# PCB_V1.net
KiCad netlist of a schematic drawn in Altium Designer
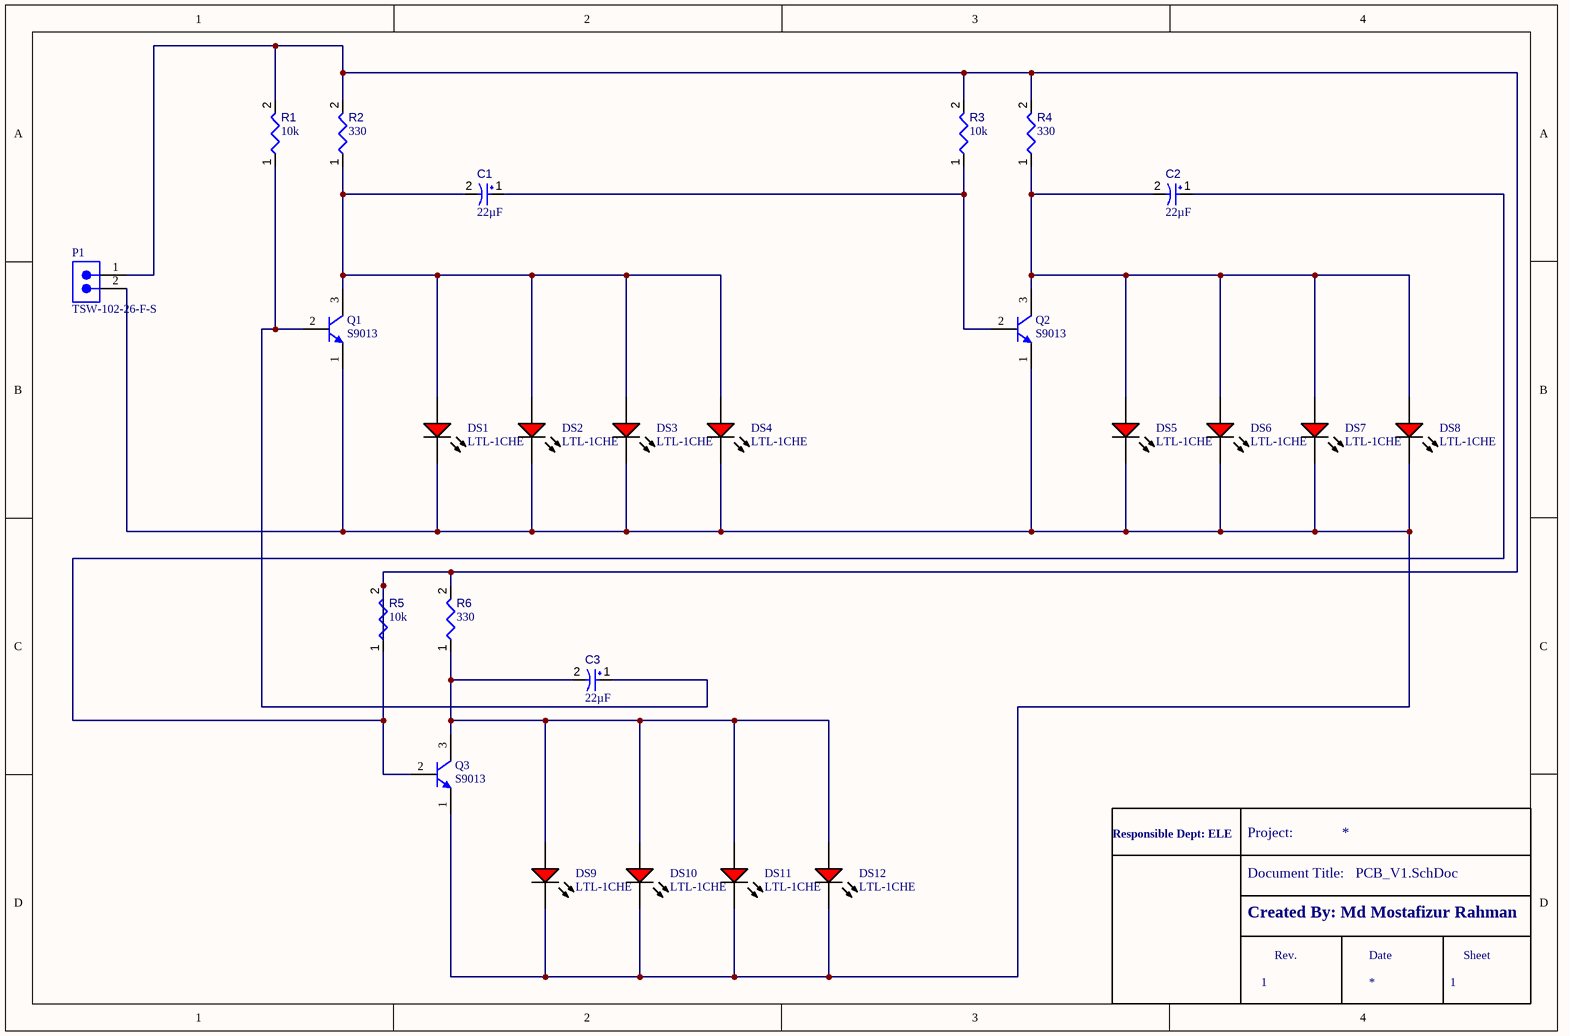
[diagram p0: PCB_V1.SchDoc]

(export (version "E")
  (design (tool "Eeschema 10.0.6"))
  (components
    (comp (ref "*") (value "HSHL Title Block") (libsource (lib "Schlib1") (part "HSHL Title Block")))
    (comp (ref "C1")
      (value "22µF")
      (footprint "CAPPR55-200-1100X500X1200")
      (description "Aluminum Electrolytic Capacitor, 22 uF, +/- 20%, 50 V, -40 to 85 degC, 2-Pin THD, RoHS, Bulk")
      (fields (field (name "MANUFACTURER") "Panasonic") (field (name "TOLERANCE") "20%"))
      (libsource (lib "Md Mostafizur Rahman") (part "CAP-P-2"))
    )
    (comp (ref "C2")
      (value "22µF")
      (footprint "CAPPR55-200-1100X500X1200")
      (description "Aluminum Electrolytic Capacitor, 22 uF, +/- 20%, 50 V, -40 to 85 degC, 2-Pin THD, RoHS, Bulk")
      (fields (field (name "MANUFACTURER") "Panasonic") (field (name "TOLERANCE") "20%"))
      (libsource (lib "Md Mostafizur Rahman") (part "CAP-P-2"))
    )
    (comp (ref "C3")
      (value "22µF")
      (footprint "CAPPR55-200-1100X500X1200")
      (description "Aluminum Electrolytic Capacitor, 22 uF, +/- 20%, 50 V, -40 to 85 degC, 2-Pin THD, RoHS, Bulk")
      (fields (field (name "MANUFACTURER") "Panasonic") (field (name "TOLERANCE") "20%"))
      (libsource (lib "Md Mostafizur Rahman") (part "CAP-P-2"))
    )
    (comp (ref "DS1")
      (value "LTL-1CHE")
      (footprint "INDPR60-254-520X380X650")
      (description "LED Uni-Color Red, 100 mW, 30 mA, -55 to 100 degC, 2-Pin THD, RoHS, Bulk")
      (fields (field (name "MANUFACTURER") "Lite-On"))
      (libsource (lib "Md Mostafizur Rahman") (part "LED-RED-AK-2"))
    )
    (comp (ref "DS2")
      (value "LTL-1CHE")
      (footprint "INDPR60-254-520X380X650")
      (description "LED Uni-Color Red, 100 mW, 30 mA, -55 to 100 degC, 2-Pin THD, RoHS, Bulk")
      (fields (field (name "MANUFACTURER") "Lite-On"))
      (libsource (lib "Md Mostafizur Rahman") (part "LED-RED-AK-2"))
    )
    (comp (ref "DS3")
      (value "LTL-1CHE")
      (footprint "INDPR60-254-520X380X650")
      (description "LED Uni-Color Red, 100 mW, 30 mA, -55 to 100 degC, 2-Pin THD, RoHS, Bulk")
      (fields (field (name "MANUFACTURER") "Lite-On"))
      (libsource (lib "Md Mostafizur Rahman") (part "LED-RED-AK-2"))
    )
    (comp (ref "DS4")
      (value "LTL-1CHE")
      (footprint "INDPR60-254-520X380X650")
      (description "LED Uni-Color Red, 100 mW, 30 mA, -55 to 100 degC, 2-Pin THD, RoHS, Bulk")
      (fields (field (name "MANUFACTURER") "Lite-On"))
      (libsource (lib "Md Mostafizur Rahman") (part "LED-RED-AK-2"))
    )
    (comp (ref "DS5")
      (value "LTL-1CHE")
      (footprint "INDPR60-254-520X380X650")
      (description "LED Uni-Color Red, 100 mW, 30 mA, -55 to 100 degC, 2-Pin THD, RoHS, Bulk")
      (fields (field (name "MANUFACTURER") "Lite-On"))
      (libsource (lib "Md Mostafizur Rahman") (part "LED-RED-AK-2"))
    )
    (comp (ref "DS6")
      (value "LTL-1CHE")
      (footprint "INDPR60-254-520X380X650")
      (description "LED Uni-Color Red, 100 mW, 30 mA, -55 to 100 degC, 2-Pin THD, RoHS, Bulk")
      (fields (field (name "MANUFACTURER") "Lite-On"))
      (libsource (lib "Md Mostafizur Rahman") (part "LED-RED-AK-2"))
    )
    (comp (ref "DS7")
      (value "LTL-1CHE")
      (footprint "INDPR60-254-520X380X650")
      (description "LED Uni-Color Red, 100 mW, 30 mA, -55 to 100 degC, 2-Pin THD, RoHS, Bulk")
      (fields (field (name "MANUFACTURER") "Lite-On"))
      (libsource (lib "Md Mostafizur Rahman") (part "LED-RED-AK-2"))
    )
    (comp (ref "DS8")
      (value "LTL-1CHE")
      (footprint "INDPR60-254-520X380X650")
      (description "LED Uni-Color Red, 100 mW, 30 mA, -55 to 100 degC, 2-Pin THD, RoHS, Bulk")
      (fields (field (name "MANUFACTURER") "Lite-On"))
      (libsource (lib "Md Mostafizur Rahman") (part "LED-RED-AK-2"))
    )
    (comp (ref "DS9")
      (value "LTL-1CHE")
      (footprint "INDPR60-254-520X380X650")
      (description "LED Uni-Color Red, 100 mW, 30 mA, -55 to 100 degC, 2-Pin THD, RoHS, Bulk")
      (fields (field (name "MANUFACTURER") "Lite-On"))
      (libsource (lib "Md Mostafizur Rahman") (part "LED-RED-AK-2"))
    )
    (comp (ref "DS10")
      (value "LTL-1CHE")
      (footprint "INDPR60-254-520X380X650")
      (description "LED Uni-Color Red, 100 mW, 30 mA, -55 to 100 degC, 2-Pin THD, RoHS, Bulk")
      (fields (field (name "MANUFACTURER") "Lite-On"))
      (libsource (lib "Md Mostafizur Rahman") (part "LED-RED-AK-2"))
    )
    (comp (ref "DS11")
      (value "LTL-1CHE")
      (footprint "INDPR60-254-520X380X650")
      (description "LED Uni-Color Red, 100 mW, 30 mA, -55 to 100 degC, 2-Pin THD, RoHS, Bulk")
      (fields (field (name "MANUFACTURER") "Lite-On"))
      (libsource (lib "Md Mostafizur Rahman") (part "LED-RED-AK-2"))
    )
    (comp (ref "DS12")
      (value "LTL-1CHE")
      (footprint "INDPR60-254-520X380X650")
      (description "LED Uni-Color Red, 100 mW, 30 mA, -55 to 100 degC, 2-Pin THD, RoHS, Bulk")
      (fields (field (name "MANUFACTURER") "Lite-On"))
      (libsource (lib "Md Mostafizur Rahman") (part "LED-RED-AK-2"))
    )
    (comp (ref "P1")
      (value "TSW-102-26-F-S")
      (footprint "SMTC-TSW-102-26-XX-S")
      (description "0.025\" SQ Post Header, Through-hole, Vertical, -55 to 125 degC, 2.54 mm Pitch, 2-Pin, Male, RoHS")
      (fields (field (name "MANUFACTURER") "Samtec"))
      (libsource (lib "Altium Content Vault") (part "SMTC-TSW-102-X-X-S-X"))
    )
    (comp (ref "Q1")
      (value "S9013")
      (footprint "JSCJ-TO-92-3_V")
      (description "Transistor, NPN, 0.1 uA, 150 MHz, 3-Pin TO-92")
      (fields (field (name "MANUFACTURER") "Jiangsu Changjiang Electronics Technology"))
      (libsource (lib "Md Mostafizur Rahman") (part "BJT-NPN-EBC-3"))
    )
    (comp (ref "Q2")
      (value "S9013")
      (footprint "JSCJ-TO-92-3_V")
      (description "Transistor, NPN, 0.1 uA, 150 MHz, 3-Pin TO-92")
      (fields (field (name "MANUFACTURER") "Jiangsu Changjiang Electronics Technology"))
      (libsource (lib "Md Mostafizur Rahman") (part "BJT-NPN-EBC-3"))
    )
    (comp (ref "Q3")
      (value "S9013")
      (footprint "JSCJ-TO-92-3_V")
      (description "Transistor, NPN, 0.1 uA, 150 MHz, 3-Pin TO-92")
      (fields (field (name "MANUFACTURER") "Jiangsu Changjiang Electronics Technology"))
      (libsource (lib "Md Mostafizur Rahman") (part "BJT-NPN-EBC-3"))
    )
    (comp (ref "R1")
      (value "10k")
      (footprint "RESA60-630X240")
      (description "Axial Resistor, 10 KOhm, +/- 1%, 0.25 W, -55 to 155 degC, 2-Pin THD, RoHS, Bulk")
      (fields (field (name "TOLERANCE") "1%") (field (name "POWER") "250mW"))
      (libsource (lib "Md Mostafizur Rahman") (part "RES-2"))
    )
    (comp (ref "R2")
      (value "330")
      (description "Fixed Resistor, Carbon Film, 0.125W, 330ohm, 250V, 5% +/-Tol, -400, 0ppm/Cel, Through Hole Mount")
      (fields (field (name "TOLERANCE") "5%") (field (name "Comment") "CF18JT330R"))
      (libsource (lib "Md Mostafizur Rahman") (part "RES-2"))
    )
    (comp (ref "R3")
      (value "10k")
      (footprint "RESA60-630X240")
      (description "Axial Resistor, 10 KOhm, +/- 1%, 0.25 W, -55 to 155 degC, 2-Pin THD, RoHS, Bulk")
      (fields (field (name "TOLERANCE") "1%") (field (name "POWER") "250mW"))
      (libsource (lib "Md Mostafizur Rahman") (part "RES-2"))
    )
    (comp (ref "R4")
      (value "330")
      (description "Fixed Resistor, Carbon Film, 0.125W, 330ohm, 250V, 5% +/-Tol, -400, 0ppm/Cel, Through Hole Mount")
      (fields (field (name "TOLERANCE") "5%") (field (name "Comment") "CF18JT330R"))
      (libsource (lib "Md Mostafizur Rahman") (part "RES-2"))
    )
    (comp (ref "R5")
      (value "10k")
      (footprint "RESA60-630X240")
      (description "Axial Resistor, 10 KOhm, +/- 1%, 0.25 W, -55 to 155 degC, 2-Pin THD, RoHS, Bulk")
      (fields (field (name "TOLERANCE") "1%") (field (name "POWER") "250mW"))
      (libsource (lib "Md Mostafizur Rahman") (part "RES-2"))
    )
    (comp (ref "R6")
      (value "330")
      (description "Fixed Resistor, Carbon Film, 0.125W, 330ohm, 250V, 5% +/-Tol, -400, 0ppm/Cel, Through Hole Mount")
      (fields (field (name "TOLERANCE") "5%") (field (name "Comment") "CF18JT330R"))
      (libsource (lib "Md Mostafizur Rahman") (part "RES-2"))
    )
  )
  (nets
    (net (code "1") (name "Net-(DS1-A)") (class "Default")
      (node (ref "C1") (pin "2") (pinfunction "2_2") (pintype "passive"))
      (node (ref "DS1") (pin "1") (pinfunction "A_1") (pintype "passive"))
      (node (ref "DS2") (pin "1") (pinfunction "A_1") (pintype "passive"))
      (node (ref "DS3") (pin "1") (pinfunction "A_1") (pintype "passive"))
      (node (ref "DS4") (pin "1") (pinfunction "A_1") (pintype "passive"))
      (node (ref "Q1") (pin "3") (pinfunction "C_3") (pintype "passive"))
      (node (ref "R2") (pin "1") (pinfunction "1_1") (pintype "passive"))
    )
    (net (code "2") (name "Net-(DS1-K)") (class "Default")
      (node (ref "DS1") (pin "2") (pinfunction "K_2") (pintype "passive"))
      (node (ref "DS10") (pin "2") (pinfunction "K_2") (pintype "passive"))
      (node (ref "DS11") (pin "2") (pinfunction "K_2") (pintype "passive"))
      (node (ref "DS12") (pin "2") (pinfunction "K_2") (pintype "passive"))
      (node (ref "DS2") (pin "2") (pinfunction "K_2") (pintype "passive"))
      (node (ref "DS3") (pin "2") (pinfunction "K_2") (pintype "passive"))
      (node (ref "DS4") (pin "2") (pinfunction "K_2") (pintype "passive"))
      (node (ref "DS5") (pin "2") (pinfunction "K_2") (pintype "passive"))
      (node (ref "DS6") (pin "2") (pinfunction "K_2") (pintype "passive"))
      (node (ref "DS7") (pin "2") (pinfunction "K_2") (pintype "passive"))
      (node (ref "DS8") (pin "2") (pinfunction "K_2") (pintype "passive"))
      (node (ref "DS9") (pin "2") (pinfunction "K_2") (pintype "passive"))
      (node (ref "P1") (pin "2") (pinfunction "2_2") (pintype "passive"))
      (node (ref "Q1") (pin "1") (pinfunction "E_1") (pintype "passive"))
      (node (ref "Q2") (pin "1") (pinfunction "E_1") (pintype "passive"))
      (node (ref "Q3") (pin "1") (pinfunction "E_1") (pintype "passive"))
    )
    (net (code "3") (name "Net-(DS5-A)") (class "Default")
      (node (ref "C2") (pin "2") (pinfunction "2_2") (pintype "passive"))
      (node (ref "DS5") (pin "1") (pinfunction "A_1") (pintype "passive"))
      (node (ref "DS6") (pin "1") (pinfunction "A_1") (pintype "passive"))
      (node (ref "DS7") (pin "1") (pinfunction "A_1") (pintype "passive"))
      (node (ref "DS8") (pin "1") (pinfunction "A_1") (pintype "passive"))
      (node (ref "Q2") (pin "3") (pinfunction "C_3") (pintype "passive"))
      (node (ref "R4") (pin "1") (pinfunction "1_1") (pintype "passive"))
    )
    (net (code "4") (name "Net-(DS10-A)") (class "Default")
      (node (ref "C3") (pin "2") (pinfunction "2_2") (pintype "passive"))
      (node (ref "DS10") (pin "1") (pinfunction "A_1") (pintype "passive"))
      (node (ref "DS11") (pin "1") (pinfunction "A_1") (pintype "passive"))
      (node (ref "DS12") (pin "1") (pinfunction "A_1") (pintype "passive"))
      (node (ref "DS9") (pin "1") (pinfunction "A_1") (pintype "passive"))
      (node (ref "Q3") (pin "3") (pinfunction "C_3") (pintype "passive"))
      (node (ref "R6") (pin "1") (pinfunction "1_1") (pintype "passive"))
    )
    (net (code "5") (name "Net-(P1-Pad1)") (class "Default")
      (node (ref "P1") (pin "1") (pinfunction "1_1") (pintype "passive"))
      (node (ref "R1") (pin "2") (pinfunction "2_2") (pintype "passive"))
      (node (ref "R2") (pin "2") (pinfunction "2_2") (pintype "passive"))
      (node (ref "R3") (pin "2") (pinfunction "2_2") (pintype "passive"))
      (node (ref "R4") (pin "2") (pinfunction "2_2") (pintype "passive"))
      (node (ref "R5") (pin "2") (pinfunction "2_2") (pintype "passive"))
      (node (ref "R6") (pin "2") (pinfunction "2_2") (pintype "passive"))
    )
    (net (code "6") (name "Net-(Q1-B)") (class "Default")
      (node (ref "C3") (pin "1") (pinfunction "1_1") (pintype "passive"))
      (node (ref "Q1") (pin "2") (pinfunction "B_2") (pintype "passive"))
      (node (ref "R1") (pin "1") (pinfunction "1_1") (pintype "passive"))
    )
    (net (code "7") (name "Net-(Q2-B)") (class "Default")
      (node (ref "C1") (pin "1") (pinfunction "1_1") (pintype "passive"))
      (node (ref "Q2") (pin "2") (pinfunction "B_2") (pintype "passive"))
      (node (ref "R3") (pin "1") (pinfunction "1_1") (pintype "passive"))
    )
    (net (code "8") (name "Net-(Q3-B)") (class "Default")
      (node (ref "C2") (pin "1") (pinfunction "1_1") (pintype "passive"))
      (node (ref "Q3") (pin "2") (pinfunction "B_2") (pintype "passive"))
      (node (ref "R5") (pin "1") (pinfunction "1_1") (pintype "passive"))
    )
  )
)
